# CAN-BUS_FD_HAT_for_Raspberry_Pi.net
KiCad netlist of a schematic drawn in EAGLE
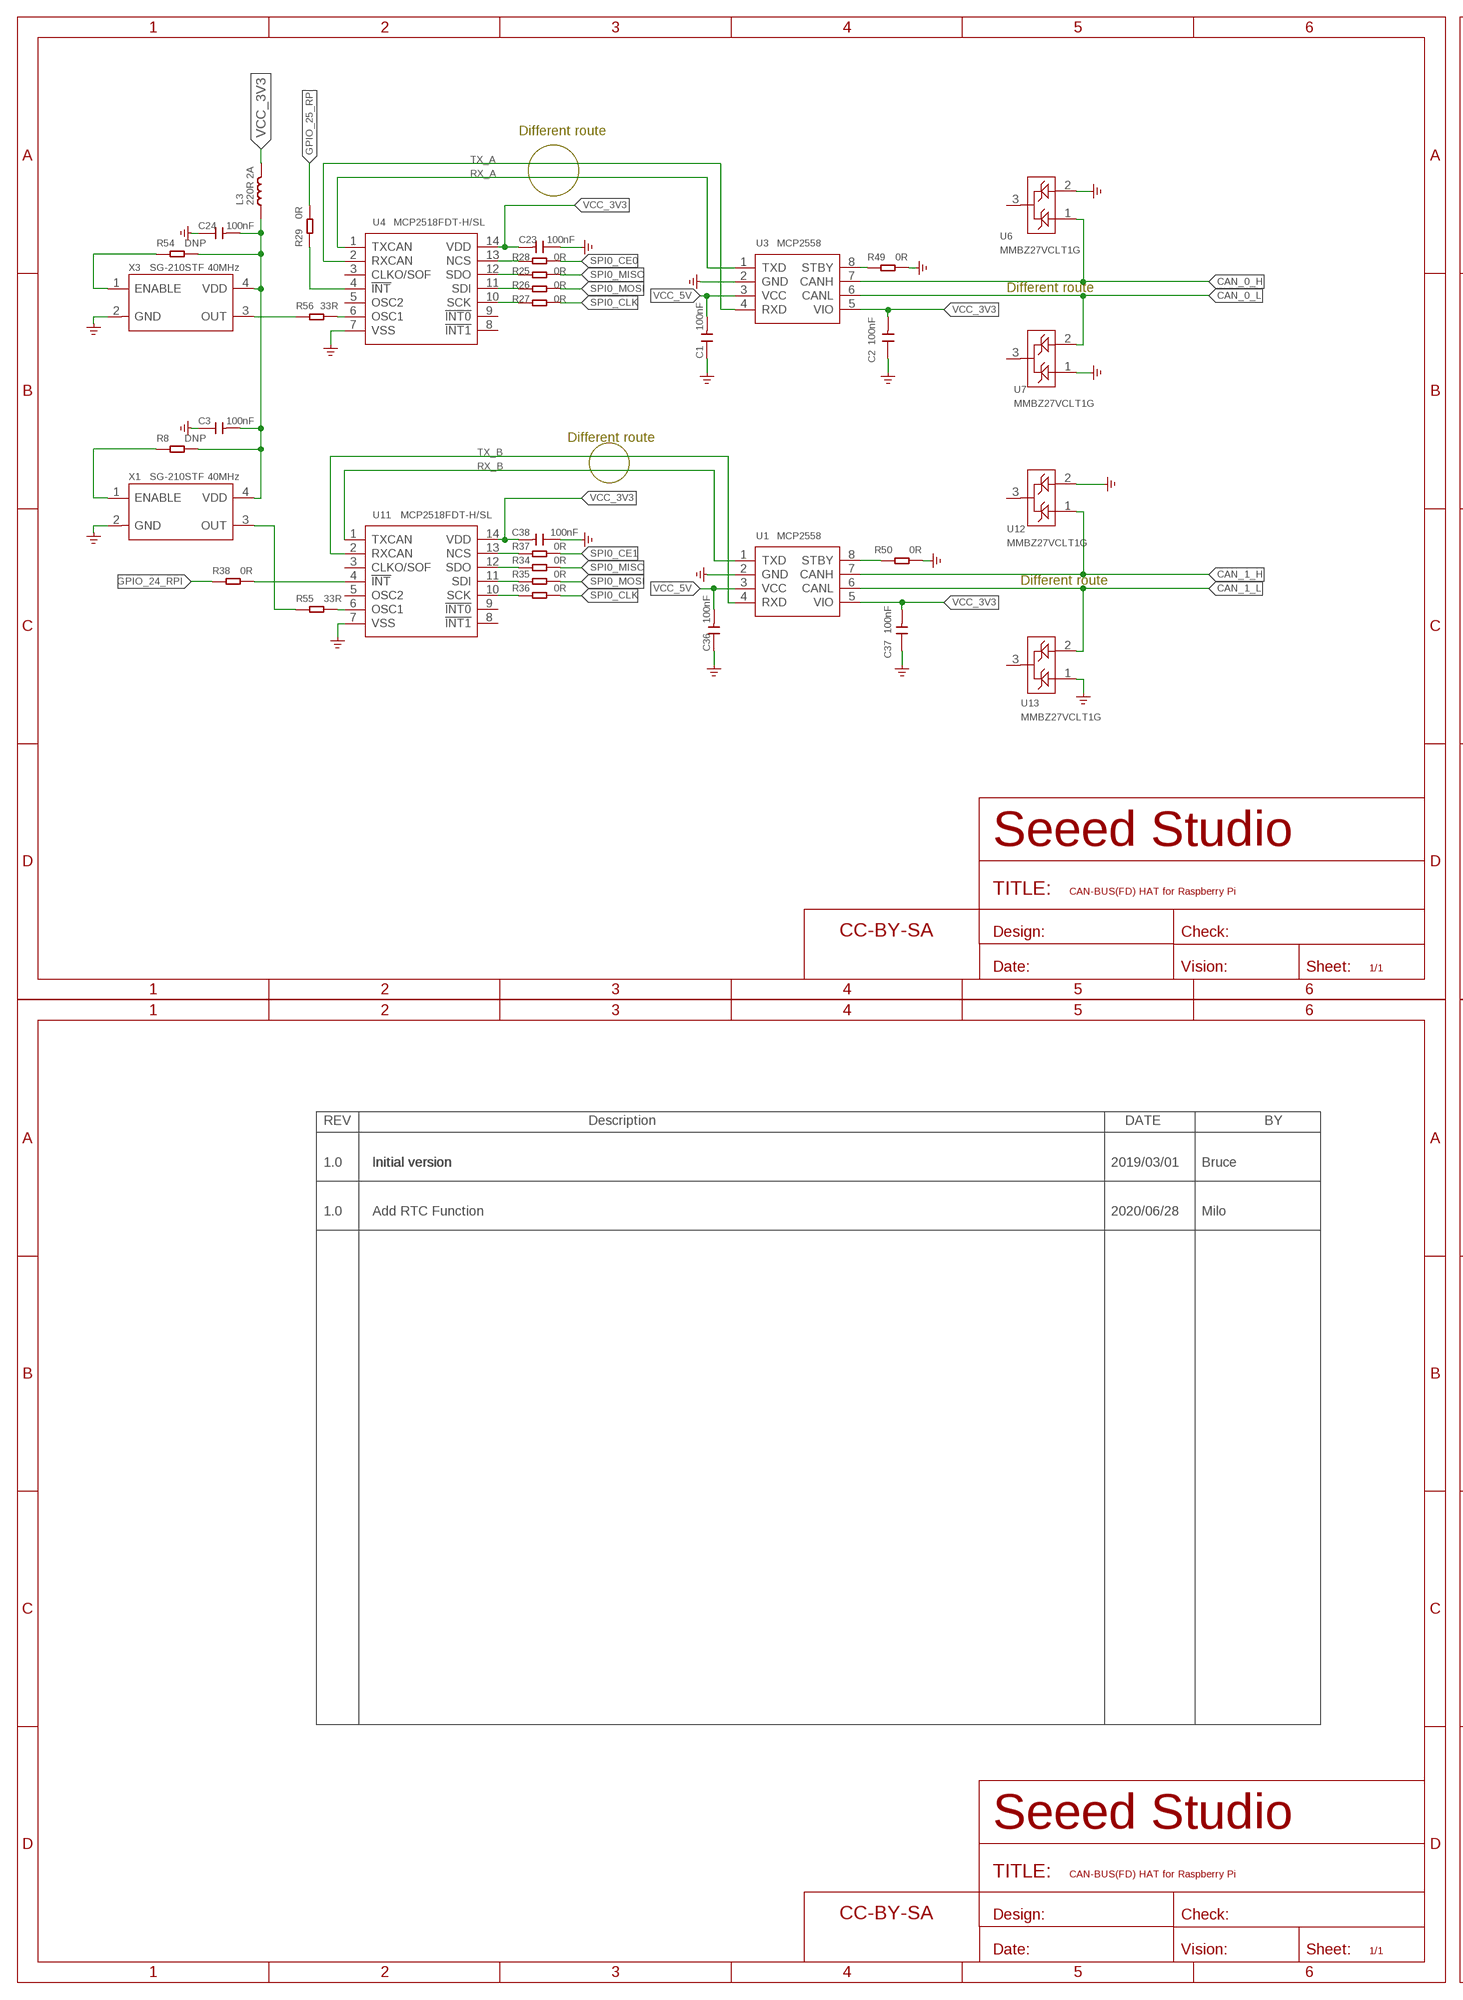
[diagram p0: schematic, sheet 1, part 1 of 2]
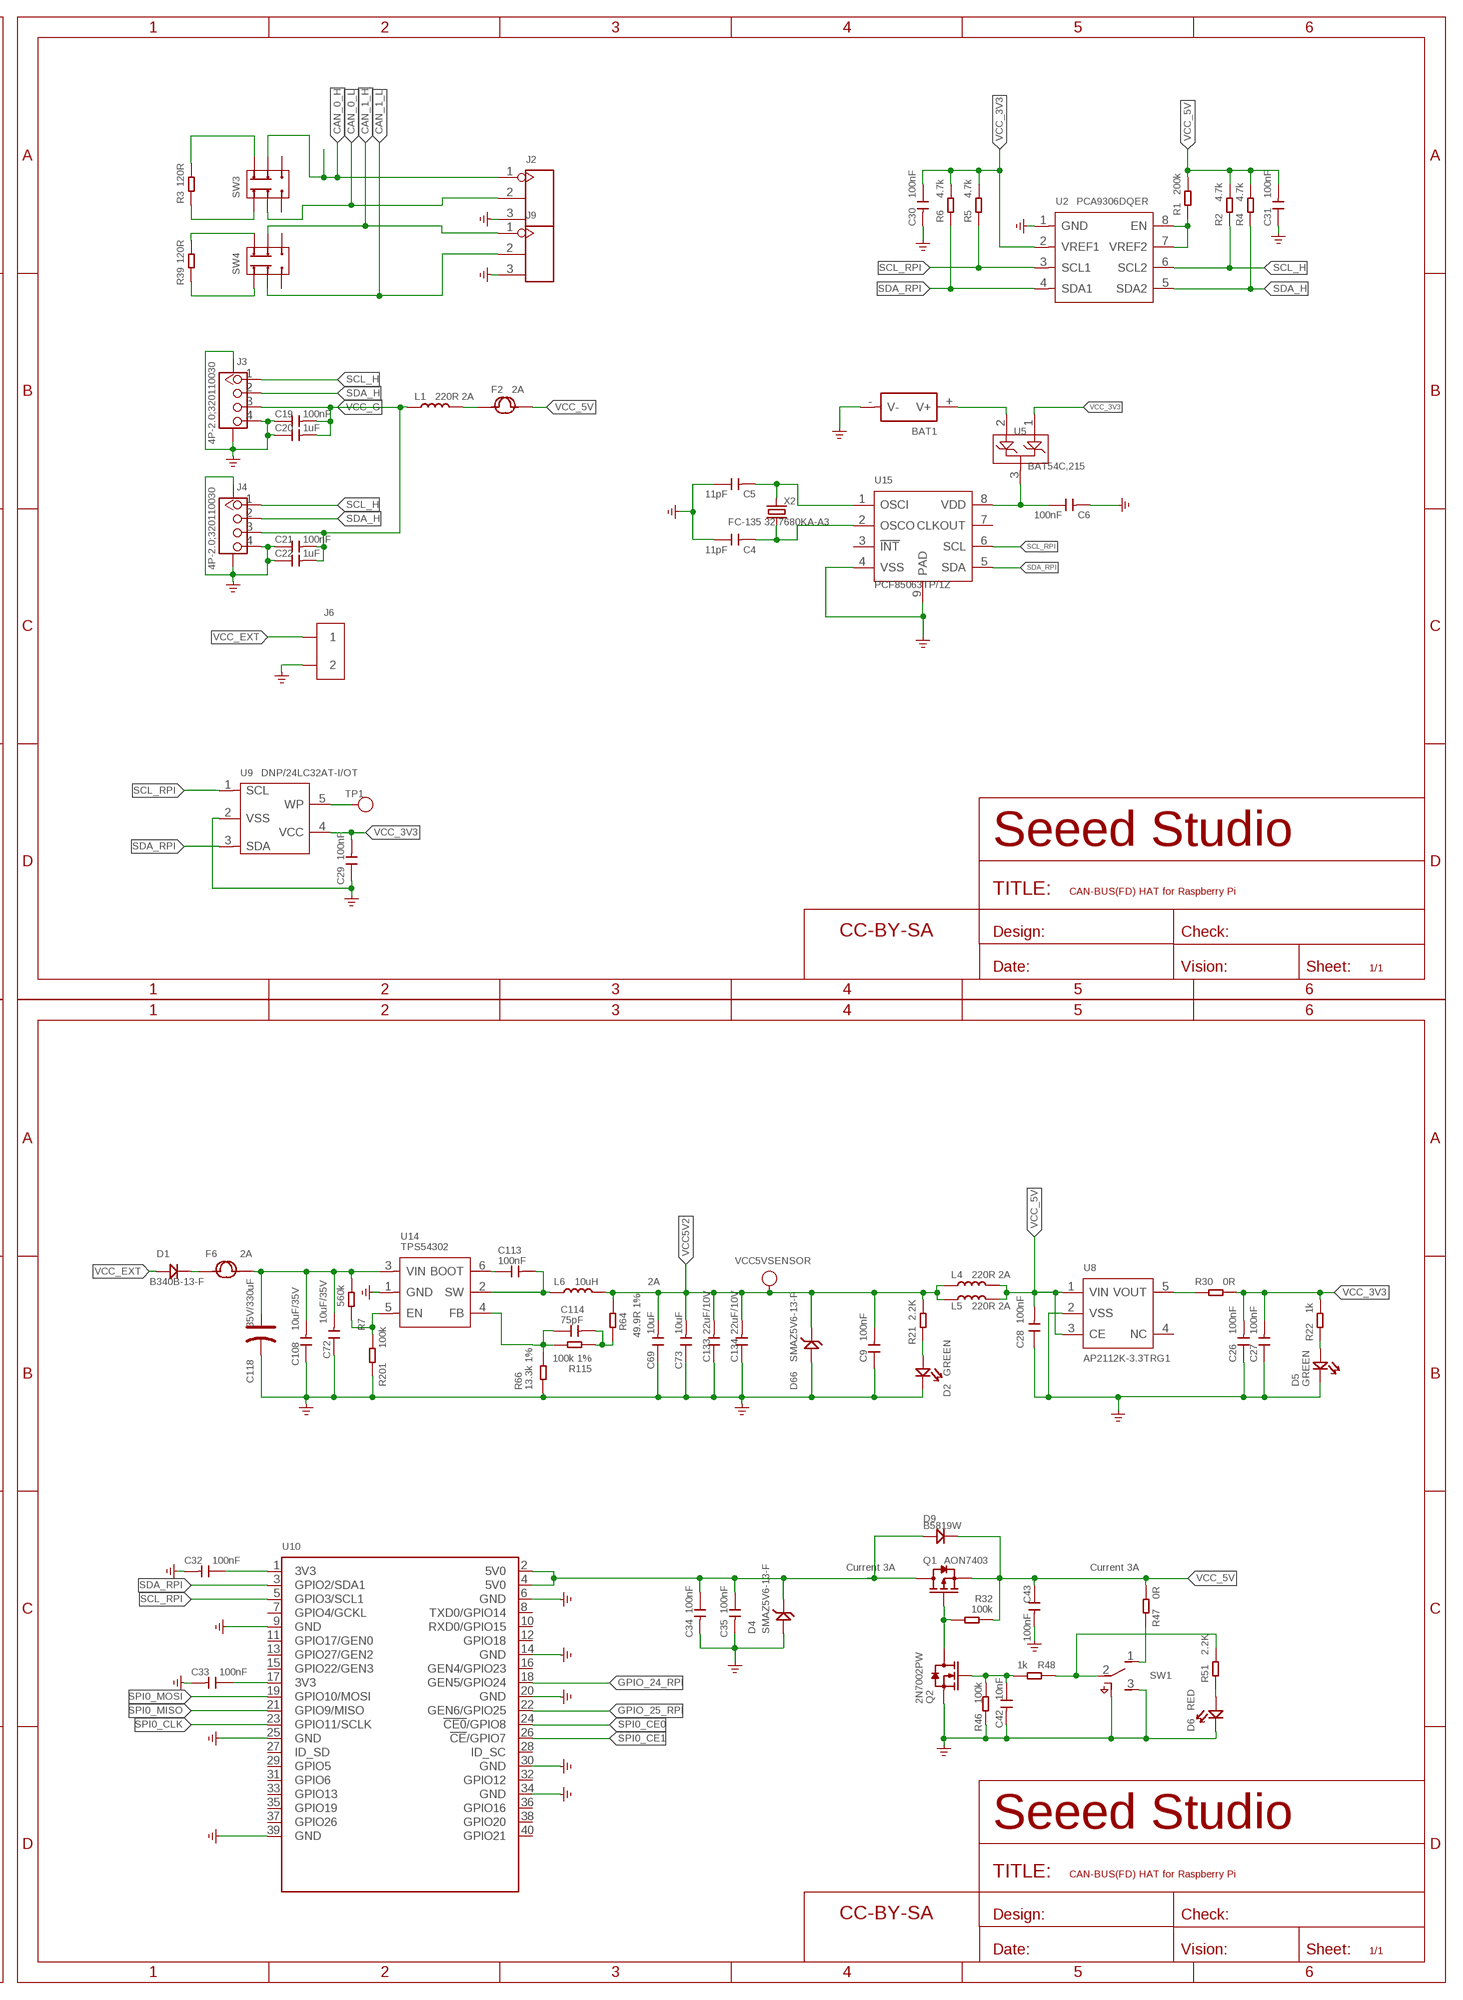
[diagram p1: schematic, sheet 1, part 2 of 2]

(export (version "E")
  (design (tool "Eeschema 10.0.6"))
  (components
    (comp (ref "BAT1")
      (value "BAT-HOLDER'SMD-1220'")
      (footprint "eagle-import:BAT2P-SMD-16.4-CR1220")
      (libsource (lib "eagle-import") (part "BAT-HOLDER'SMD-1220'"))
    )
    (comp (ref "C1")
      (value "100nF")
      (footprint "eagle-import:C0603")
      (libsource (lib "eagle-import") (part "CAP-0603"))
    )
    (comp (ref "C2")
      (value "100nF")
      (footprint "eagle-import:C0603")
      (libsource (lib "eagle-import") (part "CAP-0603"))
    )
    (comp (ref "C3")
      (value "100nF")
      (footprint "eagle-import:C0603")
      (libsource (lib "eagle-import") (part "CAP-0603"))
    )
    (comp (ref "C4")
      (value "11pF")
      (footprint "eagle-import:C0603")
      (libsource (lib "eagle-import") (part "CAP-0603"))
    )
    (comp (ref "C5")
      (value "11pF")
      (footprint "eagle-import:C0603")
      (libsource (lib "eagle-import") (part "CAP-0603"))
    )
    (comp (ref "C6")
      (value "100nF")
      (footprint "eagle-import:C0603")
      (libsource (lib "eagle-import") (part "CAP-0603"))
    )
    (comp (ref "C9")
      (value "100nF")
      (footprint "eagle-import:C0603")
      (libsource (lib "eagle-import") (part "CAP-0603"))
    )
    (comp (ref "C19")
      (value "100nF")
      (footprint "eagle-import:C0603")
      (libsource (lib "eagle-import") (part "CAP-0603"))
    )
    (comp (ref "C20")
      (value "1uF")
      (footprint "eagle-import:C0603")
      (libsource (lib "eagle-import") (part "CAP-0603"))
    )
    (comp (ref "C21")
      (value "100nF")
      (footprint "eagle-import:C0603")
      (libsource (lib "eagle-import") (part "CAP-0603"))
    )
    (comp (ref "C22")
      (value "1uF")
      (footprint "eagle-import:C0603")
      (libsource (lib "eagle-import") (part "CAP-0603"))
    )
    (comp (ref "C23")
      (value "100nF")
      (footprint "eagle-import:C0603")
      (libsource (lib "eagle-import") (part "CAP-0603"))
    )
    (comp (ref "C24")
      (value "100nF")
      (footprint "eagle-import:C0603")
      (libsource (lib "eagle-import") (part "CAP-0603"))
    )
    (comp (ref "C26")
      (value "100nF")
      (footprint "eagle-import:C0603")
      (libsource (lib "eagle-import") (part "CAP-0603"))
    )
    (comp (ref "C27")
      (value "100nF")
      (footprint "eagle-import:C0603")
      (libsource (lib "eagle-import") (part "CAP-0603"))
    )
    (comp (ref "C28")
      (value "100nF")
      (footprint "eagle-import:C0603")
      (libsource (lib "eagle-import") (part "CAP-0603"))
    )
    (comp (ref "C29")
      (value "100nF")
      (footprint "eagle-import:C0603")
      (libsource (lib "eagle-import") (part "CAP-0603"))
    )
    (comp (ref "C30")
      (value "100nF")
      (footprint "eagle-import:C0603")
      (libsource (lib "eagle-import") (part "CAP-0603"))
    )
    (comp (ref "C31")
      (value "100nF")
      (footprint "eagle-import:C0603")
      (libsource (lib "eagle-import") (part "CAP-0603"))
    )
    (comp (ref "C32")
      (value "100nF")
      (footprint "eagle-import:C0603")
      (libsource (lib "eagle-import") (part "CAP-0603"))
    )
    (comp (ref "C33")
      (value "100nF")
      (footprint "eagle-import:C0603")
      (libsource (lib "eagle-import") (part "CAP-0603"))
    )
    (comp (ref "C34")
      (value "100nF")
      (footprint "eagle-import:C0603")
      (libsource (lib "eagle-import") (part "CAP-0603"))
    )
    (comp (ref "C35")
      (value "100nF")
      (footprint "eagle-import:C0603")
      (libsource (lib "eagle-import") (part "CAP-0603"))
    )
    (comp (ref "C36")
      (value "100nF")
      (footprint "eagle-import:C0603")
      (libsource (lib "eagle-import") (part "CAP-0603"))
    )
    (comp (ref "C37")
      (value "100nF")
      (footprint "eagle-import:C0603")
      (libsource (lib "eagle-import") (part "CAP-0603"))
    )
    (comp (ref "C38")
      (value "100nF")
      (footprint "eagle-import:C0603")
      (libsource (lib "eagle-import") (part "CAP-0603"))
    )
    (comp (ref "C42")
      (value "10nF")
      (footprint "eagle-import:C0603")
      (libsource (lib "eagle-import") (part "CAP-0603"))
    )
    (comp (ref "C43")
      (value "100nF")
      (footprint "eagle-import:C0603")
      (libsource (lib "eagle-import") (part "CAP-0603"))
    )
    (comp (ref "C69")
      (value "10uF")
      (footprint "eagle-import:C0805")
      (libsource (lib "eagle-import") (part "CAP-0805"))
    )
    (comp (ref "C72")
      (value "10uF/35V")
      (footprint "eagle-import:C0805")
      (libsource (lib "eagle-import") (part "CAP-0805"))
    )
    (comp (ref "C73")
      (value "10uF")
      (footprint "eagle-import:C0805")
      (libsource (lib "eagle-import") (part "CAP-0805"))
    )
    (comp (ref "C108")
      (value "10uF/35V")
      (footprint "eagle-import:C0805")
      (libsource (lib "eagle-import") (part "CAP-0805"))
    )
    (comp (ref "C113")
      (value "100nF")
      (footprint "eagle-import:C0603")
      (libsource (lib "eagle-import") (part "CAP-0603"))
    )
    (comp (ref "C114")
      (value "75pF")
      (footprint "eagle-import:C0603")
      (libsource (lib "eagle-import") (part "CAP-0603"))
    )
    (comp (ref "C118")
      (value "35V/330uF")
      (footprint "eagle-import:ELECTRO-SMD-E-7.8MM")
      (libsource (lib "eagle-import") (part "CAP-POLAR-ELECTRO-E"))
    )
    (comp (ref "C133")
      (value "22uF/10V")
      (footprint "eagle-import:C1206")
      (libsource (lib "eagle-import") (part "CAP-1206"))
    )
    (comp (ref "C134")
      (value "22uF/10V")
      (footprint "eagle-import:C1206")
      (libsource (lib "eagle-import") (part "CAP-1206"))
    )
    (comp (ref "D1")
      (value "B340B-13-F")
      (footprint "eagle-import:DO-214AA")
      (libsource (lib "eagle-import") (part "Discrete-new_DIODE'SMB'"))
    )
    (comp (ref "D2")
      (value "GREEN")
      (footprint "eagle-import:LED-0603")
      (libsource (lib "eagle-import") (part "LED'0603'"))
    )
    (comp (ref "D4")
      (value "SMAZ5V6-13-F")
      (footprint "eagle-import:DO-214AC")
      (libsource (lib "eagle-import") (part "D-ZENER-2P-SMA"))
    )
    (comp (ref "D5")
      (value "GREEN")
      (footprint "eagle-import:LED-0603")
      (libsource (lib "eagle-import") (part "LED'0603'"))
    )
    (comp (ref "D6")
      (value "RED")
      (footprint "eagle-import:LED-0603")
      (libsource (lib "eagle-import") (part "LED'0603'"))
    )
    (comp (ref "D9")
      (value "B5819W")
      (footprint "eagle-import:SOD-123")
      (libsource (lib "eagle-import") (part "Discrete-new_DIODE'1206'"))
    )
    (comp (ref "D66")
      (value "SMAZ5V6-13-F")
      (footprint "eagle-import:DO-214AC")
      (libsource (lib "eagle-import") (part "D-ZENER-2P-SMA"))
    )
    (comp (ref "F2")
      (value "2A")
      (footprint "eagle-import:FS1210")
      (libsource (lib "eagle-import") (part "FUSE+'1210'"))
    )
    (comp (ref "F6")
      (value "2A")
      (footprint "eagle-import:F1812")
      (libsource (lib "eagle-import") (part "FUSE'1812'"))
    )
    (comp (ref "FR1")
      (value "SEEEDSTUDIO-OPEN-SCH-FRAME")
      (footprint "eagle-import:SEEEDSTUDIO-PCB-FRAME")
      (libsource (lib "eagle-import") (part "SEEEDSTUDIO-OPEN-SCH-FRAME"))
    )
    (comp (ref "FR2")
      (value "SEEEDSTUDIO-OPEN-SCH-FRAME")
      (footprint "eagle-import:SEEEDSTUDIO-PCB-FRAME")
      (libsource (lib "eagle-import") (part "SEEEDSTUDIO-OPEN-SCH-FRAME"))
    )
    (comp (ref "FR3")
      (value "SEEEDSTUDIO-OPEN-SCH-FRAME")
      (footprint "eagle-import:SEEEDSTUDIO-PCB-FRAME")
      (libsource (lib "eagle-import") (part "SEEEDSTUDIO-OPEN-SCH-FRAME"))
    )
    (comp (ref "FR5")
      (value "SEEEDSTUDIO-OPEN-SCH-FRAME")
      (footprint "eagle-import:SEEEDSTUDIO-PCB-FRAME")
      (libsource (lib "eagle-import") (part "SEEEDSTUDIO-OPEN-SCH-FRAME"))
    )
    (comp (ref "J2")
      (value "SCREW-TERMINAL-3P'3.5'")
      (footprint "eagle-import:H3-3.5-11.5X7.0MM")
      (libsource (lib "eagle-import") (part "SCREW-TERMINAL-3P'3.5'"))
    )
    (comp (ref "J3")
      (value "4P-2.0;320110030")
      (footprint "eagle-import:HW4-SMD-2.0")
      (libsource (lib "eagle-import") (part "GROVE-CONNECTOR-SMD'DD'"))
    )
    (comp (ref "J4")
      (value "4P-2.0;320110030")
      (footprint "eagle-import:HW4-SMD-2.0")
      (libsource (lib "eagle-import") (part "GROVE-CONNECTOR-SMD'DD'"))
    )
    (comp (ref "J6")
      (value "SCREW-TERMINAL-2P'3.5'")
      (footprint "eagle-import:H2-3.5-7.0X7.0MM")
      (libsource (lib "eagle-import") (part "SCREW-TERMINAL-2P'3.5'"))
    )
    (comp (ref "J9")
      (value "SCREW-TERMINAL-3P'3.5'")
      (footprint "eagle-import:H3-3.5-11.5X7.0MM")
      (libsource (lib "eagle-import") (part "SCREW-TERMINAL-3P'3.5'"))
    )
    (comp (ref "L1")
      (value "220R 2A")
      (footprint "eagle-import:L0805")
      (libsource (lib "eagle-import") (part "INDUCTOR/FERRITE-BEAD'0805'"))
    )
    (comp (ref "L3")
      (value "220R 2A")
      (footprint "eagle-import:L0805")
      (libsource (lib "eagle-import") (part "INDUCTOR/FERRITE-BEAD'0805'"))
    )
    (comp (ref "L4")
      (value "220R 2A")
      (footprint "eagle-import:L0805")
      (libsource (lib "eagle-import") (part "INDUCTOR/FERRITE-BEAD'0805'"))
    )
    (comp (ref "L5")
      (value "220R 2A")
      (footprint "eagle-import:L0805")
      (libsource (lib "eagle-import") (part "INDUCTOR/FERRITE-BEAD'0805'"))
    )
    (comp (ref "L6")
      (value "10uH")
      (footprint "eagle-import:L8040")
      (libsource (lib "eagle-import") (part "INDUCTOR-8040"))
    )
    (comp (ref "Q1")
      (value "AON7403")
      (footprint "eagle-import:DFN8P-0.65-3X3X0.8MM")
      (libsource (lib "eagle-import") (part "MOSFET-P-AON7403"))
    )
    (comp (ref "Q2")
      (value "2N7002PW")
      (footprint "eagle-import:SOT-23")
      (libsource (lib "eagle-import") (part "MOSFET-N'SOT23'"))
    )
    (comp (ref "R1")
      (value "200k")
      (footprint "eagle-import:R0603")
      (libsource (lib "eagle-import") (part "RES-0603"))
    )
    (comp (ref "R2")
      (value "4.7k")
      (footprint "eagle-import:R0603")
      (libsource (lib "eagle-import") (part "RES-0603"))
    )
    (comp (ref "R3")
      (value "120R")
      (footprint "eagle-import:R1206")
      (libsource (lib "eagle-import") (part "RES-1206"))
    )
    (comp (ref "R4")
      (value "4.7k")
      (footprint "eagle-import:R0603")
      (libsource (lib "eagle-import") (part "RES-0603"))
    )
    (comp (ref "R5")
      (value "4.7k")
      (footprint "eagle-import:R0603")
      (libsource (lib "eagle-import") (part "RES-0603"))
    )
    (comp (ref "R6")
      (value "4.7k")
      (footprint "eagle-import:R0603")
      (libsource (lib "eagle-import") (part "RES-0603"))
    )
    (comp (ref "R7")
      (value "560k")
      (footprint "eagle-import:R0603")
      (libsource (lib "eagle-import") (part "RES-0603"))
    )
    (comp (ref "R8")
      (value "DNP")
      (footprint "eagle-import:0603")
      (libsource (lib "eagle-import") (part "R-0603"))
    )
    (comp (ref "R21")
      (value "2.2K")
      (footprint "eagle-import:0603")
      (libsource (lib "eagle-import") (part "R-0603"))
    )
    (comp (ref "R22")
      (value "1k")
      (footprint "eagle-import:0603")
      (libsource (lib "eagle-import") (part "R-0603"))
    )
    (comp (ref "R25")
      (value "0R")
      (footprint "eagle-import:0603")
      (libsource (lib "eagle-import") (part "R-0603"))
    )
    (comp (ref "R26")
      (value "0R")
      (footprint "eagle-import:0603")
      (libsource (lib "eagle-import") (part "R-0603"))
    )
    (comp (ref "R27")
      (value "0R")
      (footprint "eagle-import:0603")
      (libsource (lib "eagle-import") (part "R-0603"))
    )
    (comp (ref "R28")
      (value "0R")
      (footprint "eagle-import:0603")
      (libsource (lib "eagle-import") (part "R-0603"))
    )
    (comp (ref "R29")
      (value "0R")
      (footprint "eagle-import:0603")
      (libsource (lib "eagle-import") (part "R-0603"))
    )
    (comp (ref "R30")
      (value "0R")
      (footprint "eagle-import:R0603")
      (libsource (lib "eagle-import") (part "RES-0603"))
    )
    (comp (ref "R32")
      (value "100k")
      (footprint "eagle-import:0603")
      (libsource (lib "eagle-import") (part "R-0603"))
    )
    (comp (ref "R34")
      (value "0R")
      (footprint "eagle-import:0603")
      (libsource (lib "eagle-import") (part "R-0603"))
    )
    (comp (ref "R35")
      (value "0R")
      (footprint "eagle-import:0603")
      (libsource (lib "eagle-import") (part "R-0603"))
    )
    (comp (ref "R36")
      (value "0R")
      (footprint "eagle-import:0603")
      (libsource (lib "eagle-import") (part "R-0603"))
    )
    (comp (ref "R37")
      (value "0R")
      (footprint "eagle-import:0603")
      (libsource (lib "eagle-import") (part "R-0603"))
    )
    (comp (ref "R38")
      (value "0R")
      (footprint "eagle-import:0603")
      (libsource (lib "eagle-import") (part "R-0603"))
    )
    (comp (ref "R39")
      (value "120R")
      (footprint "eagle-import:R1206")
      (libsource (lib "eagle-import") (part "RES-1206"))
    )
    (comp (ref "R46")
      (value "100k")
      (footprint "eagle-import:0603")
      (libsource (lib "eagle-import") (part "R-0603"))
    )
    (comp (ref "R47")
      (value "0R")
      (footprint "eagle-import:0603")
      (libsource (lib "eagle-import") (part "R-0603"))
    )
    (comp (ref "R48")
      (value "1k")
      (footprint "eagle-import:0603")
      (libsource (lib "eagle-import") (part "R-0603"))
    )
    (comp (ref "R49")
      (value "0R")
      (footprint "eagle-import:0603")
      (libsource (lib "eagle-import") (part "R-0603"))
    )
    (comp (ref "R50")
      (value "0R")
      (footprint "eagle-import:0603")
      (libsource (lib "eagle-import") (part "R-0603"))
    )
    (comp (ref "R51")
      (value "2.2K")
      (footprint "eagle-import:0603")
      (libsource (lib "eagle-import") (part "R-0603"))
    )
    (comp (ref "R54")
      (value "DNP")
      (footprint "eagle-import:0603")
      (libsource (lib "eagle-import") (part "R-0603"))
    )
    (comp (ref "R55")
      (value "33R")
      (footprint "eagle-import:0603")
      (libsource (lib "eagle-import") (part "R-0603"))
    )
    (comp (ref "R56")
      (value "33R")
      (footprint "eagle-import:0603")
      (libsource (lib "eagle-import") (part "R-0603"))
    )
    (comp (ref "R64")
      (value "49.9R 1%")
      (footprint "eagle-import:R0603")
      (libsource (lib "eagle-import") (part "RES-0603"))
    )
    (comp (ref "R66")
      (value "13.3k 1%")
      (footprint "eagle-import:R0603")
      (libsource (lib "eagle-import") (part "RES-0603"))
    )
    (comp (ref "R115")
      (value "100k 1%")
      (footprint "eagle-import:R0603")
      (libsource (lib "eagle-import") (part "RES-0603"))
    )
    (comp (ref "R201")
      (value "100k")
      (footprint "eagle-import:R0603")
      (libsource (lib "eagle-import") (part "RES-0603"))
    )
    (comp (ref "SW1")
      (value "SWITCH-3+4P-311030001")
      (footprint "eagle-import:SW7-SMD-L6.7X2.7X3.2MM")
      (libsource (lib "eagle-import") (part "SWITCH-3+4P-311030001"))
    )
    (comp (ref "SW3")
      (value "SWITCH-2CH-6P-311010004")
      (footprint "eagle-import:SW6-2.54-9.0X3.5X3.2+2.0MM")
      (libsource (lib "eagle-import") (part "SWITCH-2CH-6P-311010004"))
    )
    (comp (ref "SW4")
      (value "SWITCH-2CH-6P-311010004")
      (footprint "eagle-import:SW6-2.54-9.0X3.5X3.2+2.0MM")
      (libsource (lib "eagle-import") (part "SWITCH-2CH-6P-311010004"))
    )
    (comp (ref "TP1")
      (value "DNP")
      (footprint "eagle-import:TP-D45MIL")
      (libsource (lib "eagle-import") (part "TEST-POINT'4545'"))
    )
    (comp (ref "U1")
      (value "MCP2558")
      (footprint "eagle-import:SOIC8-1.27-5X4MM")
      (libsource (lib "eagle-import") (part "TRANSCEIVER-ATA6561'GAQW'"))
    )
    (comp (ref "U2")
      (value "PCA9306DQER")
      (footprint "eagle-import:X2SON8-0.35-1.4X1X0.37MM")
      (libsource (lib "eagle-import") (part "TRANSLATOR-PCA9306DQER"))
    )
    (comp (ref "U3")
      (value "MCP2558")
      (footprint "eagle-import:SOIC8-1.27-5X4MM")
      (libsource (lib "eagle-import") (part "TRANSCEIVER-ATA6561'GAQW'"))
    )
    (comp (ref "U4")
      (value "MCP2518FDT-H/SL")
      (footprint "eagle-import:SOIC14-1.27-8.65X3.9MM")
      (libsource (lib "eagle-import") (part "INTERFACE-MCP2517FD'H/SL'"))
    )
    (comp (ref "U5")
      (value "BAT54C,215")
      (footprint "eagle-import:SOT-23")
      (libsource (lib "eagle-import") (part "DIODE-BAT54C"))
    )
    (comp (ref "U6")
      (value "MMBZ27VCLT1G")
      (footprint "eagle-import:SOT-23")
      (libsource (lib "eagle-import") (part "DIODE-BAT54C"))
    )
    (comp (ref "U7")
      (value "MMBZ27VCLT1G")
      (footprint "eagle-import:SOT-23")
      (libsource (lib "eagle-import") (part "DIODE-BAT54C"))
    )
    (comp (ref "U8")
      (value "AP2112K-3.3TRG1")
      (footprint "eagle-import:SOT-25")
      (libsource (lib "eagle-import") (part "PMIC-XC6220-SOT-25"))
    )
    (comp (ref "U9")
      (value "DNP/24LC32AT-I/OT")
      (footprint "eagle-import:SOT-23-5")
      (libsource (lib "eagle-import") (part "MEMORY-24LC32A'310090051'"))
    )
    (comp (ref "U10")
      (value "RPI-ZERO-SMD/NP")
      (footprint "eagle-import:H2X20-SMD_NP-2.54")
      (libsource (lib "eagle-import") (part "RPI-ZERO-SMD/NP"))
    )
    (comp (ref "U11")
      (value "MCP2518FDT-H/SL")
      (footprint "eagle-import:SOIC14-1.27-8.65X3.9MM")
      (libsource (lib "eagle-import") (part "INTERFACE-MCP2517FD'H/SL'"))
    )
    (comp (ref "U12")
      (value "MMBZ27VCLT1G")
      (footprint "eagle-import:SOT-23")
      (libsource (lib "eagle-import") (part "DIODE-BAT54C"))
    )
    (comp (ref "U13")
      (value "MMBZ27VCLT1G")
      (footprint "eagle-import:SOT-23")
      (libsource (lib "eagle-import") (part "DIODE-BAT54C"))
    )
    (comp (ref "U14")
      (value "TPS54302")
      (footprint "eagle-import:SOT-23-6")
      (libsource (lib "eagle-import") (part "PMIC-TPS54302"))
    )
    (comp (ref "U15")
      (value "PCF85063TP/1Z")
      (footprint "eagle-import:HWSON8-0.5-2X3X0.75MM")
      (libsource (lib "eagle-import") (part "RTC-PCF85063TP"))
    )
    (comp (ref "VCC5VSENSOR")
      (value "DNP")
      (footprint "eagle-import:TP-D45MIL")
      (libsource (lib "eagle-import") (part "TEST-POINT'4545'"))
    )
    (comp (ref "X1")
      (value "SG-210STF 40MHz")
      (footprint "eagle-import:X4-SMD-2.5X2.0X1.0MM")
      (libsource (lib "eagle-import") (part "CRYSTAL-OSCILLATOR-2520"))
    )
    (comp (ref "X2")
      (value "FC-135 32.7680KA-A3")
      (footprint "eagle-import:X2-SMD-3.2X1.5X0.55MM")
      (libsource (lib "eagle-import") (part "CRYSTAL-2P-3215"))
    )
    (comp (ref "X3")
      (value "SG-210STF 40MHz")
      (footprint "eagle-import:X4-SMD-2.5X2.0X1.0MM")
      (libsource (lib "eagle-import") (part "CRYSTAL-OSCILLATOR-2520"))
    )
  )
  (nets
    (net (code "1") (name "/RX_A") (class "Default")
      (node (ref "U3") (pin "1") (pinfunction "TXD_1") (pintype "bidirectional"))
      (node (ref "U4") (pin "1") (pinfunction "TXCAN_1") (pintype "bidirectional"))
    )
    (net (code "2") (name "/RX_B") (class "Default")
      (node (ref "U1") (pin "1") (pinfunction "TXD_1") (pintype "bidirectional"))
      (node (ref "U11") (pin "1") (pinfunction "TXCAN_1") (pintype "bidirectional"))
    )
    (net (code "3") (name "/TX_A") (class "Default")
      (node (ref "U3") (pin "4") (pinfunction "RXD_4") (pintype "bidirectional"))
      (node (ref "U4") (pin "2") (pinfunction "RXCAN_2") (pintype "bidirectional"))
    )
    (net (code "4") (name "/TX_B") (class "Default")
      (node (ref "U1") (pin "4") (pinfunction "RXD_4") (pintype "bidirectional"))
      (node (ref "U11") (pin "2") (pinfunction "RXCAN_2") (pintype "bidirectional"))
    )
    (net (code "5") (name "CAN_0_H") (class "Default")
      (node (ref "J2") (pin "1") (pinfunction "P$1_1") (pintype "bidirectional"))
      (node (ref "SW3") (pin "COM2") (pinfunction "COM2_COM2") (pintype "bidirectional"))
      (node (ref "U3") (pin "7") (pinfunction "CANH_7") (pintype "bidirectional"))
      (node (ref "U6") (pin "1") (pinfunction "P$1_1") (pintype "bidirectional"))
    )
    (net (code "6") (name "CAN_0_L") (class "Default")
      (node (ref "J2") (pin "2") (pinfunction "P$2_2") (pintype "bidirectional"))
      (node (ref "SW3") (pin "COM1") (pinfunction "COM1_COM1") (pintype "bidirectional"))
      (node (ref "U3") (pin "6") (pinfunction "CANL_6") (pintype "bidirectional"))
      (node (ref "U7") (pin "2") (pinfunction "P$2_2") (pintype "bidirectional"))
    )
    (net (code "7") (name "CAN_1_H") (class "Default")
      (node (ref "J9") (pin "1") (pinfunction "P$1_1") (pintype "bidirectional"))
      (node (ref "SW4") (pin "COM2") (pinfunction "COM2_COM2") (pintype "bidirectional"))
      (node (ref "U1") (pin "7") (pinfunction "CANH_7") (pintype "bidirectional"))
      (node (ref "U12") (pin "1") (pinfunction "P$1_1") (pintype "bidirectional"))
    )
    (net (code "8") (name "CAN_1_L") (class "Default")
      (node (ref "J9") (pin "2") (pinfunction "P$2_2") (pintype "bidirectional"))
      (node (ref "SW4") (pin "COM1") (pinfunction "COM1_COM1") (pintype "bidirectional"))
      (node (ref "U1") (pin "6") (pinfunction "CANL_6") (pintype "bidirectional"))
      (node (ref "U13") (pin "2") (pinfunction "P$2_2") (pintype "bidirectional"))
    )
    (net (code "9") (name "GND_POWER") (class "Default")
      (node (ref "BAT1") (pin "-") (pinfunction "V-_-") (pintype "bidirectional"))
      (node (ref "C1") (pin "1") (pinfunction "1_1") (pintype "passive"))
      (node (ref "C108") (pin "1") (pinfunction "1_1") (pintype "passive"))
      (node (ref "C118") (pin "-") (pinfunction "-_-") (pintype "passive"))
      (node (ref "C133") (pin "1") (pinfunction "1_1") (pintype "passive"))
      (node (ref "C134") (pin "1") (pinfunction "1_1") (pintype "passive"))
      (node (ref "C19") (pin "1") (pinfunction "1_1") (pintype "passive"))
      (node (ref "C2") (pin "1") (pinfunction "1_1") (pintype "passive"))
      (node (ref "C20") (pin "1") (pinfunction "1_1") (pintype "passive"))
      (node (ref "C21") (pin "1") (pinfunction "1_1") (pintype "passive"))
      (node (ref "C22") (pin "1") (pinfunction "1_1") (pintype "passive"))
      (node (ref "C23") (pin "1") (pinfunction "1_1") (pintype "passive"))
      (node (ref "C24") (pin "1") (pinfunction "1_1") (pintype "passive"))
      (node (ref "C26") (pin "1") (pinfunction "1_1") (pintype "passive"))
      (node (ref "C27") (pin "1") (pinfunction "1_1") (pintype "passive"))
      (node (ref "C28") (pin "1") (pinfunction "1_1") (pintype "passive"))
      (node (ref "C29") (pin "1") (pinfunction "1_1") (pintype "passive"))
      (node (ref "C3") (pin "1") (pinfunction "1_1") (pintype "passive"))
      (node (ref "C30") (pin "2") (pinfunction "2_2") (pintype "passive"))
      (node (ref "C31") (pin "1") (pinfunction "1_1") (pintype "passive"))
      (node (ref "C32") (pin "2") (pinfunction "2_2") (pintype "passive"))
      (node (ref "C33") (pin "2") (pinfunction "2_2") (pintype "passive"))
      (node (ref "C34") (pin "2") (pinfunction "2_2") (pintype "passive"))
      (node (ref "C35") (pin "2") (pinfunction "2_2") (pintype "passive"))
      (node (ref "C36") (pin "1") (pinfunction "1_1") (pintype "passive"))
      (node (ref "C37") (pin "1") (pinfunction "1_1") (pintype "passive"))
      (node (ref "C38") (pin "1") (pinfunction "1_1") (pintype "passive"))
      (node (ref "C4") (pin "1") (pinfunction "1_1") (pintype "passive"))
      (node (ref "C42") (pin "2") (pinfunction "2_2") (pintype "passive"))
      (node (ref "C43") (pin "2") (pinfunction "2_2") (pintype "passive"))
      (node (ref "C5") (pin "1") (pinfunction "1_1") (pintype "passive"))
      (node (ref "C6") (pin "2") (pinfunction "2_2") (pintype "passive"))
      (node (ref "C69") (pin "1") (pinfunction "1_1") (pintype "passive"))
      (node (ref "C72") (pin "1") (pinfunction "1_1") (pintype "passive"))
      (node (ref "C73") (pin "1") (pinfunction "1_1") (pintype "passive"))
      (node (ref "C9") (pin "1") (pinfunction "1_1") (pintype "passive"))
      (node (ref "D2") (pin "-") (pinfunction "-_-") (pintype "passive"))
      (node (ref "D4") (pin "1") (pinfunction "+_1") (pintype "bidirectional"))
      (node (ref "D5") (pin "-") (pinfunction "-_-") (pintype "passive"))
      (node (ref "D6") (pin "-") (pinfunction "-_-") (pintype "passive"))
      (node (ref "D66") (pin "1") (pinfunction "+_1") (pintype "bidirectional"))
      (node (ref "J2") (pin "3") (pinfunction "P$3_3") (pintype "bidirectional"))
      (node (ref "J3") (pin "4") (pinfunction "4_4") (pintype "bidirectional"))
      (node (ref "J3") (pin "SS1") (pinfunction "SS1_SS1") (pintype "bidirectional"))
      (node (ref "J3") (pin "SS2") (pinfunction "SS2_SS2") (pintype "bidirectional"))
      (node (ref "J4") (pin "4") (pinfunction "4_4") (pintype "bidirectional"))
      (node (ref "J4") (pin "SS1") (pinfunction "SS1_SS1") (pintype "bidirectional"))
      (node (ref "J4") (pin "SS2") (pinfunction "SS2_SS2") (pintype "bidirectional"))
      (node (ref "J6") (pin "2") (pinfunction "2_2") (pintype "bidirectional"))
      (node (ref "J9") (pin "3") (pinfunction "P$3_3") (pintype "bidirectional"))
      (node (ref "Q2") (pin "2") (pinfunction "S_2") (pintype "passive"))
      (node (ref "R201") (pin "1") (pinfunction "1_1") (pintype "passive"))
      (node (ref "R46") (pin "1") (pinfunction "1_1") (pintype "passive"))
      (node (ref "R49") (pin "2") (pinfunction "2_2") (pintype "passive"))
      (node (ref "R50") (pin "2") (pinfunction "2_2") (pintype "passive"))
      (node (ref "R66") (pin "1") (pinfunction "1_1") (pintype "passive"))
      (node (ref "SW1") (pin "3") (pinfunction "B_3") (pintype "bidirectional"))
      (node (ref "SW1") (pin "SS1") (pinfunction "SS2_SS1") (pintype "bidirectional"))
      (node (ref "SW1") (pin "SS2") (pinfunction "SS2_SS2") (pintype "bidirectional"))
      (node (ref "SW1") (pin "SS3") (pinfunction "SS2_SS3") (pintype "bidirectional"))
      (node (ref "SW1") (pin "SS4") (pinfunction "SS2_SS4") (pintype "bidirectional"))
      (node (ref "U1") (pin "2") (pinfunction "GND_2") (pintype "bidirectional"))
      (node (ref "U10") (pin "14") (pinfunction "GND_14") (pintype "power_in"))
      (node (ref "U10") (pin "20") (pinfunction "GND_20") (pintype "power_in"))
      (node (ref "U10") (pin "25") (pinfunction "GND_25") (pintype "power_in"))
      (node (ref "U10") (pin "30") (pinfunction "GND_30") (pintype "power_in"))
      (node (ref "U10") (pin "34") (pinfunction "GND_34") (pintype "power_in"))
      (node (ref "U10") (pin "39") (pinfunction "GND_39") (pintype "power_in"))
      (node (ref "U10") (pin "6") (pinfunction "GND_6") (pintype "power_in"))
      (node (ref "U10") (pin "9") (pinfunction "GND_9") (pintype "power_in"))
      (node (ref "U11") (pin "7") (pinfunction "VSS_7") (pintype "bidirectional"))
      (node (ref "U12") (pin "2") (pinfunction "P$2_2") (pintype "bidirectional"))
      (node (ref "U13") (pin "1") (pinfunction "P$1_1") (pintype "bidirectional"))
      (node (ref "U14") (pin "1") (pinfunction "GND_1") (pintype "bidirectional"))
      (node (ref "U15") (pin "4") (pinfunction "VSS_4") (pintype "bidirectional"))
      (node (ref "U15") (pin "9") (pinfunction "PAD_9") (pintype "bidirectional"))
      (node (ref "U2") (pin "1") (pinfunction "GND_1") (pintype "bidirectional"))
      (node (ref "U3") (pin "2") (pinfunction "GND_2") (pintype "bidirectional"))
      (node (ref "U4") (pin "7") (pinfunction "VSS_7") (pintype "bidirectional"))
      (node (ref "U6") (pin "2") (pinfunction "P$2_2") (pintype "bidirectional"))
      (node (ref "U7") (pin "1") (pinfunction "P$1_1") (pintype "bidirectional"))
      (node (ref "U8") (pin "2") (pinfunction "VSS_2") (pintype "bidirectional"))
      (node (ref "U9") (pin "2") (pinfunction "VSS_2") (pintype "bidirectional"))
      (node (ref "X1") (pin "2") (pinfunction "GND_2") (pintype "bidirectional"))
      (node (ref "X3") (pin "2") (pinfunction "GND_2") (pintype "bidirectional"))
    )
    (net (code "10") (name "GPIO_24_RPI") (class "Default")
      (node (ref "R38") (pin "2") (pinfunction "2_2") (pintype "passive"))
      (node (ref "U10") (pin "18") (pinfunction "GEN5/GPIO24_18") (pintype "bidirectional"))
    )
    (net (code "11") (name "GPIO_25_RPI") (class "Default")
      (node (ref "R29") (pin "2") (pinfunction "2_2") (pintype "passive"))
      (node (ref "U10") (pin "22") (pinfunction "GEN6/GPIO25_22") (pintype "bidirectional"))
    )
    (net (code "12") (name "Net-(BAT1-V+)") (class "Default")
      (node (ref "BAT1") (pin "+") (pinfunction "V+_+") (pintype "bidirectional"))
      (node (ref "U5") (pin "2") (pinfunction "P$2_2") (pintype "bidirectional"))
    )
    (net (code "13") (name "Net-(C32-Pad1)") (class "Default")
      (node (ref "C32") (pin "1") (pinfunction "1_1") (pintype "passive"))
      (node (ref "U10") (pin "1") (pinfunction "3V3_1") (pintype "power_in"))
    )
    (net (code "14") (name "Net-(C33-Pad1)") (class "Default")
      (node (ref "C33") (pin "1") (pinfunction "1_1") (pintype "passive"))
      (node (ref "U10") (pin "17") (pinfunction "3V3_17") (pintype "power_in"))
    )
    (net (code "15") (name "Net-(C114-Pad2)") (class "Default")
      (node (ref "C114") (pin "2") (pinfunction "2_2") (pintype "passive"))
      (node (ref "R115") (pin "1") (pinfunction "1_1") (pintype "passive"))
      (node (ref "R64") (pin "1") (pinfunction "1_1") (pintype "passive"))
    )
    (net (code "16") (name "Net-(D1--)") (class "Default")
      (node (ref "D1") (pin "2") (pinfunction "-_2") (pintype "passive"))
      (node (ref "F6") (pin "1") (pinfunction "1_1") (pintype "bidirectional"))
    )
    (net (code "17") (name "Net-(D2-Pad+)") (class "Default")
      (node (ref "D2") (pin "+") (pinfunction "+_+") (pintype "passive"))
      (node (ref "R21") (pin "1") (pinfunction "1_1") (pintype "passive"))
    )
    (net (code "18") (name "Net-(D4--)") (class "Default")
      (node (ref "C34") (pin "1") (pinfunction "1_1") (pintype "passive"))
      (node (ref "C35") (pin "1") (pinfunction "1_1") (pintype "passive"))
      (node (ref "D4") (pin "2") (pinfunction "-_2") (pintype "bidirectional"))
      (node (ref "D9") (pin "+") (pinfunction "+_+") (pintype "passive"))
      (node (ref "Q1") (pin "5") (pinfunction "D_5") (pintype "passive"))
      (node (ref "Q1") (pin "6") (pinfunction "D_6") (pintype "passive"))
      (node (ref "Q1") (pin "7") (pinfunction "D_7") (pintype "passive"))
      (node (ref "Q1") (pin "8") (pinfunction "D_8") (pintype "passive"))
      (node (ref "U10") (pin "2") (pinfunction "5V0_2") (pintype "power_in"))
      (node (ref "U10") (pin "4") (pinfunction "5V0_4") (pintype "power_in"))
    )
    (net (code "19") (name "Net-(D5-Pad+)") (class "Default")
      (node (ref "D5") (pin "+") (pinfunction "+_+") (pintype "passive"))
      (node (ref "R22") (pin "1") (pinfunction "1_1") (pintype "passive"))
    )
    (net (code "20") (name "Net-(D6-Pad+)") (class "Default")
      (node (ref "D6") (pin "+") (pinfunction "+_+") (pintype "passive"))
      (node (ref "R51") (pin "1") (pinfunction "1_1") (pintype "passive"))
    )
    (net (code "21") (name "Net-(F2-Pad1)") (class "Default")
      (node (ref "F2") (pin "1") (pinfunction "1_1") (pintype "bidirectional"))
      (node (ref "L1") (pin "2") (pinfunction "2_2") (pintype "passive"))
    )
    (net (code "22") (name "Net-(Q1-G)") (class "Default")
      (node (ref "Q1") (pin "4") (pinfunction "G_4") (pintype "passive"))
      (node (ref "Q2") (pin "3") (pinfunction "D_3") (pintype "passive"))
      (node (ref "R32") (pin "2") (pinfunction "2_2") (pintype "passive"))
    )
    (net (code "23") (name "Net-(Q2-G)") (class "Default")
      (node (ref "C42") (pin "1") (pinfunction "1_1") (pintype "passive"))
      (node (ref "Q2") (pin "1") (pinfunction "G_1") (pintype "passive"))
      (node (ref "R46") (pin "2") (pinfunction "2_2") (pintype "passive"))
      (node (ref "R48") (pin "2") (pinfunction "2_2") (pintype "passive"))
    )
    (net (code "24") (name "Net-(R3-Pad1)") (class "Default")
      (node (ref "R3") (pin "1") (pinfunction "1_1") (pintype "passive"))
      (node (ref "SW3") (pin "CH2A") (pinfunction "CH2A_CH2A") (pintype "bidirectional"))
    )
    (net (code "25") (name "Net-(R3-Pad2)") (class "Default")
      (node (ref "R3") (pin "2") (pinfunction "2_2") (pintype "passive"))
      (node (ref "SW3") (pin "CH1A") (pinfunction "CH1A_CH1A") (pintype "bidirectional"))
    )
    (net (code "26") (name "Net-(R39-Pad1)") (class "Default")
      (node (ref "R39") (pin "1") (pinfunction "1_1") (pintype "passive"))
      (node (ref "SW4") (pin "CH2A") (pinfunction "CH2A_CH2A") (pintype "bidirectional"))
    )
    (net (code "27") (name "Net-(R39-Pad2)") (class "Default")
      (node (ref "R39") (pin "2") (pinfunction "2_2") (pintype "passive"))
      (node (ref "SW4") (pin "CH1A") (pinfunction "CH1A_CH1A") (pintype "bidirectional"))
    )
    (net (code "28") (name "Net-(SW1-A)") (class "Default")
      (node (ref "R47") (pin "1") (pinfunction "1_1") (pintype "passive"))
      (node (ref "SW1") (pin "1") (pinfunction "A_1") (pintype "bidirectional"))
    )
    (net (code "29") (name "Net-(SW1-COM)") (class "Default")
      (node (ref "R48") (pin "1") (pinfunction "1_1") (pintype "passive"))
      (node (ref "R51") (pin "2") (pinfunction "2_2") (pintype "passive"))
      (node (ref "SW1") (pin "2") (pinfunction "COM_2") (pintype "bidirectional"))
    )
    (net (code "30") (name "Net-(U1-STBY)") (class "Default")
      (node (ref "R50") (pin "1") (pinfunction "1_1") (pintype "passive"))
      (node (ref "U1") (pin "8") (pinfunction "STBY_8") (pintype "bidirectional"))
    )
    (net (code "31") (name "Net-(U2-EN)") (class "Default")
      (node (ref "R1") (pin "1") (pinfunction "1_1") (pintype "passive"))
      (node (ref "U2") (pin "7") (pinfunction "VREF2_7") (pintype "bidirectional"))
      (node (ref "U2") (pin "8") (pinfunction "EN_8") (pintype "bidirectional"))
    )
    (net (code "32") (name "Net-(U3-STBY)") (class "Default")
      (node (ref "R49") (pin "1") (pinfunction "1_1") (pintype "passive"))
      (node (ref "U3") (pin "8") (pinfunction "STBY_8") (pintype "bidirectional"))
    )
    (net (code "33") (name "Net-(U4-NCS)") (class "Default")
      (node (ref "R28") (pin "1") (pinfunction "1_1") (pintype "passive"))
      (node (ref "U4") (pin "13") (pinfunction "NCS_13") (pintype "bidirectional"))
    )
    (net (code "34") (name "Net-(U4-OSC1)") (class "Default")
      (node (ref "R56") (pin "1") (pinfunction "1_1") (pintype "passive"))
      (node (ref "U4") (pin "6") (pinfunction "OSC1_6") (pintype "bidirectional"))
    )
    (net (code "35") (name "Net-(U4-SCK)") (class "Default")
      (node (ref "R27") (pin "1") (pinfunction "1_1") (pintype "passive"))
      (node (ref "U4") (pin "10") (pinfunction "SCK_10") (pintype "bidirectional"))
    )
    (net (code "36") (name "Net-(U4-SDI)") (class "Default")
      (node (ref "R26") (pin "1") (pinfunction "1_1") (pintype "passive"))
      (node (ref "U4") (pin "11") (pinfunction "SDI_11") (pintype "bidirectional"))
    )
    (net (code "37") (name "Net-(U4-SDO)") (class "Default")
      (node (ref "R25") (pin "1") (pinfunction "1_1") (pintype "passive"))
      (node (ref "U4") (pin "12") (pinfunction "SDO_12") (pintype "bidirectional"))
    )
    (net (code "38") (name "Net-(U4-~{INT})") (class "Default")
      (node (ref "R29") (pin "1") (pinfunction "1_1") (pintype "passive"))
      (node (ref "U4") (pin "4") (pinfunction "~{INT}_4") (pintype "bidirectional"))
    )
    (net (code "39") (name "Net-(U8-VOUT)") (class "Default")
      (node (ref "R30") (pin "1") (pinfunction "1_1") (pintype "passive"))
      (node (ref "U8") (pin "5") (pinfunction "VOUT_5") (pintype "bidirectional"))
    )
    (net (code "40") (name "Net-(U9-WP)") (class "Default")
      (node (ref "TP1") (pin "T") (pinfunction "T_T") (pintype "bidirectional"))
      (node (ref "U9") (pin "5") (pinfunction "WP_5") (pintype "bidirectional"))
    )
    (net (code "41") (name "Net-(U11-NCS)") (class "Default")
      (node (ref "R37") (pin "1") (pinfunction "1_1") (pintype "passive"))
      (node (ref "U11") (pin "13") (pinfunction "NCS_13") (pintype "bidirectional"))
    )
    (net (code "42") (name "Net-(U11-OSC1)") (class "Default")
      (node (ref "R55") (pin "1") (pinfunction "1_1") (pintype "passive"))
      (node (ref "U11") (pin "6") (pinfunction "OSC1_6") (pintype "bidirectional"))
    )
    (net (code "43") (name "Net-(U11-SCK)") (class "Default")
      (node (ref "R36") (pin "1") (pinfunction "1_1") (pintype "passive"))
      (node (ref "U11") (pin "10") (pinfunction "SCK_10") (pintype "bidirectional"))
    )
    (net (code "44") (name "Net-(U11-SDI)") (class "Default")
      (node (ref "R35") (pin "1") (pinfunction "1_1") (pintype "passive"))
      (node (ref "U11") (pin "11") (pinfunction "SDI_11") (pintype "bidirectional"))
    )
    (net (code "45") (name "Net-(U11-SDO)") (class "Default")
      (node (ref "R34") (pin "1") (pinfunction "1_1") (pintype "passive"))
      (node (ref "U11") (pin "12") (pinfunction "SDO_12") (pintype "bidirectional"))
    )
    (net (code "46") (name "Net-(U11-~{INT})") (class "Default")
      (node (ref "R38") (pin "1") (pinfunction "1_1") (pintype "passive"))
      (node (ref "U11") (pin "4") (pinfunction "~{INT}_4") (pintype "bidirectional"))
    )
    (net (code "47") (name "Net-(U14-BOOT)") (class "Default")
      (node (ref "C113") (pin "1") (pinfunction "1_1") (pintype "passive"))
      (node (ref "U14") (pin "6") (pinfunction "BOOT_6") (pintype "bidirectional"))
    )
    (net (code "48") (name "Net-(U14-EN)") (class "Default")
      (node (ref "R201") (pin "2") (pinfunction "2_2") (pintype "passive"))
      (node (ref "R7") (pin "1") (pinfunction "1_1") (pintype "passive"))
      (node (ref "U14") (pin "5") (pinfunction "EN_5") (pintype "bidirectional"))
    )
    (net (code "49") (name "Net-(U14-FB)") (class "Default")
      (node (ref "C114") (pin "1") (pinfunction "1_1") (pintype "passive"))
      (node (ref "R115") (pin "2") (pinfunction "2_2") (pintype "passive"))
      (node (ref "R66") (pin "2") (pinfunction "2_2") (pintype "passive"))
      (node (ref "U14") (pin "4") (pinfunction "FB_4") (pintype "bidirectional"))
    )
    (net (code "50") (name "Net-(U14-SW)") (class "Default")
      (node (ref "C113") (pin "2") (pinfunction "2_2") (pintype "passive"))
      (node (ref "L6") (pin "1") (pinfunction "1_1") (pintype "passive"))
      (node (ref "U14") (pin "2") (pinfunction "SW_2") (pintype "bidirectional"))
    )
    (net (code "51") (name "Net-(U14-VIN)") (class "Default")
      (node (ref "C108") (pin "2") (pinfunction "2_2") (pintype "passive"))
      (node (ref "C118") (pin "+") (pinfunction "+_+") (pintype "passive"))
      (node (ref "C72") (pin "2") (pinfunction "2_2") (pintype "passive"))
      (node (ref "F6") (pin "2") (pinfunction "2_2") (pintype "bidirectional"))
      (node (ref "R7") (pin "2") (pinfunction "2_2") (pintype "passive"))
      (node (ref "U14") (pin "3") (pinfunction "VIN_3") (pintype "bidirectional"))
    )
    (net (code "52") (name "Net-(U15-OSCI)") (class "Default")
      (node (ref "C5") (pin "2") (pinfunction "2_2") (pintype "passive"))
      (node (ref "U15") (pin "1") (pinfunction "OSCI_1") (pintype "bidirectional"))
      (node (ref "X2") (pin "2") (pinfunction "2_2") (pintype "passive"))
    )
    (net (code "53") (name "Net-(U15-OSCO)") (class "Default")
      (node (ref "C4") (pin "2") (pinfunction "2_2") (pintype "passive"))
      (node (ref "U15") (pin "2") (pinfunction "OSCO_2") (pintype "bidirectional"))
      (node (ref "X2") (pin "1") (pinfunction "1_1") (pintype "passive"))
    )
    (net (code "54") (name "Net-(U15-VDD)") (class "Default")
      (node (ref "C6") (pin "1") (pinfunction "1_1") (pintype "passive"))
      (node (ref "U15") (pin "8") (pinfunction "VDD_8") (pintype "bidirectional"))
      (node (ref "U5") (pin "3") (pinfunction "P$3_3") (pintype "bidirectional"))
    )
    (net (code "55") (name "Net-(X1-ENABLE)") (class "Default")
      (node (ref "R8") (pin "2") (pinfunction "2_2") (pintype "passive"))
      (node (ref "X1") (pin "1") (pinfunction "ENABLE_1") (pintype "bidirectional"))
    )
    (net (code "56") (name "Net-(X1-OUT)") (class "Default")
      (node (ref "R55") (pin "2") (pinfunction "2_2") (pintype "passive"))
      (node (ref "X1") (pin "3") (pinfunction "OUT_3") (pintype "bidirectional"))
    )
    (net (code "57") (name "Net-(X1-VDD)") (class "Default")
      (node (ref "C24") (pin "2") (pinfunction "2_2") (pintype "passive"))
      (node (ref "C3") (pin "2") (pinfunction "2_2") (pintype "passive"))
      (node (ref "L3") (pin "1") (pinfunction "1_1") (pintype "passive"))
      (node (ref "R54") (pin "1") (pinfunction "1_1") (pintype "passive"))
      (node (ref "R8") (pin "1") (pinfunction "1_1") (pintype "passive"))
      (node (ref "X1") (pin "4") (pinfunction "VDD_4") (pintype "bidirectional"))
      (node (ref "X3") (pin "4") (pinfunction "VDD_4") (pintype "bidirectional"))
    )
    (net (code "58") (name "Net-(X3-ENABLE)") (class "Default")
      (node (ref "R54") (pin "2") (pinfunction "2_2") (pintype "passive"))
      (node (ref "X3") (pin "1") (pinfunction "ENABLE_1") (pintype "bidirectional"))
    )
    (net (code "59") (name "Net-(X3-OUT)") (class "Default")
      (node (ref "R56") (pin "2") (pinfunction "2_2") (pintype "passive"))
      (node (ref "X3") (pin "3") (pinfunction "OUT_3") (pintype "bidirectional"))
    )
    (net (code "60") (name "SCL_H") (class "Default")
      (node (ref "J3") (pin "1") (pinfunction "1_1") (pintype "bidirectional"))
      (node (ref "J4") (pin "1") (pinfunction "1_1") (pintype "bidirectional"))
      (node (ref "R2") (pin "1") (pinfunction "1_1") (pintype "passive"))
      (node (ref "U2") (pin "6") (pinfunction "SCL2_6") (pintype "bidirectional"))
    )
    (net (code "61") (name "SCL_RPI") (class "Default")
      (node (ref "R5") (pin "1") (pinfunction "1_1") (pintype "passive"))
      (node (ref "U10") (pin "5") (pinfunction "GPIO3/SCL1_5") (pintype "bidirectional"))
      (node (ref "U15") (pin "6") (pinfunction "SCL_6") (pintype "bidirectional"))
      (node (ref "U2") (pin "3") (pinfunction "SCL1_3") (pintype "bidirectional"))
      (node (ref "U9") (pin "1") (pinfunction "SCL_1") (pintype "bidirectional"))
    )
    (net (code "62") (name "SDA_H") (class "Default")
      (node (ref "J3") (pin "2") (pinfunction "2_2") (pintype "bidirectional"))
      (node (ref "J4") (pin "2") (pinfunction "2_2") (pintype "bidirectional"))
      (node (ref "R4") (pin "1") (pinfunction "1_1") (pintype "passive"))
      (node (ref "U2") (pin "5") (pinfunction "SDA2_5") (pintype "bidirectional"))
    )
    (net (code "63") (name "SDA_RPI") (class "Default")
      (node (ref "R6") (pin "1") (pinfunction "1_1") (pintype "passive"))
      (node (ref "U10") (pin "3") (pinfunction "GPIO2/SDA1_3") (pintype "bidirectional"))
      (node (ref "U15") (pin "5") (pinfunction "SDA_5") (pintype "bidirectional"))
      (node (ref "U2") (pin "4") (pinfunction "SDA1_4") (pintype "bidirectional"))
      (node (ref "U9") (pin "3") (pinfunction "SDA_3") (pintype "bidirectional"))
    )
    (net (code "64") (name "SPI0_CE0") (class "Default")
      (node (ref "R28") (pin "2") (pinfunction "2_2") (pintype "passive"))
      (node (ref "U10") (pin "24") (pinfunction "~{CE0}/GPIO8_24") (pintype "bidirectional"))
    )
    (net (code "65") (name "SPI0_CE1") (class "Default")
      (node (ref "R37") (pin "2") (pinfunction "2_2") (pintype "passive"))
      (node (ref "U10") (pin "26") (pinfunction "~{CE}/GPIO7_26") (pintype "bidirectional"))
    )
    (net (code "66") (name "SPI0_CLK") (class "Default")
      (node (ref "R27") (pin "2") (pinfunction "2_2") (pintype "passive"))
      (node (ref "R36") (pin "2") (pinfunction "2_2") (pintype "passive"))
      (node (ref "U10") (pin "23") (pinfunction "GPIO11/SCLK_23") (pintype "bidirectional"))
    )
    (net (code "67") (name "SPI0_MISO") (class "Default")
      (node (ref "R25") (pin "2") (pinfunction "2_2") (pintype "passive"))
      (node (ref "R34") (pin "2") (pinfunction "2_2") (pintype "passive"))
      (node (ref "U10") (pin "21") (pinfunction "GPIO9/MISO_21") (pintype "bidirectional"))
    )
    (net (code "68") (name "SPI0_MOSI") (class "Default")
      (node (ref "R26") (pin "2") (pinfunction "2_2") (pintype "passive"))
      (node (ref "R35") (pin "2") (pinfunction "2_2") (pintype "passive"))
      (node (ref "U10") (pin "19") (pinfunction "GPIO10/MOSI_19") (pintype "bidirectional"))
    )
    (net (code "69") (name "VCC5V2") (class "Default")
      (node (ref "C133") (pin "2") (pinfunction "2_2") (pintype "passive"))
      (node (ref "C134") (pin "2") (pinfunction "2_2") (pintype "passive"))
      (node (ref "C69") (pin "2") (pinfunction "2_2") (pintype "passive"))
      (node (ref "C73") (pin "2") (pinfunction "2_2") (pintype "passive"))
      (node (ref "C9") (pin "2") (pinfunction "2_2") (pintype "passive"))
      (node (ref "D66") (pin "2") (pinfunction "-_2") (pintype "bidirectional"))
      (node (ref "L4") (pin "1") (pinfunction "1_1") (pintype "passive"))
      (node (ref "L5") (pin "1") (pinfunction "1_1") (pintype "passive"))
      (node (ref "L6") (pin "2") (pinfunction "2_2") (pintype "passive"))
      (node (ref "R21") (pin "2") (pinfunction "2_2") (pintype "passive"))
      (node (ref "R64") (pin "2") (pinfunction "2_2") (pintype "passive"))
      (node (ref "VCC5VSENSOR") (pin "T") (pinfunction "T_T") (pintype "bidirectional"))
    )
    (net (code "70") (name "VCC_3V3") (class "Default")
      (node (ref "C2") (pin "2") (pinfunction "2_2") (pintype "passive"))
      (node (ref "C23") (pin "2") (pinfunction "2_2") (pintype "passive"))
      (node (ref "C26") (pin "2") (pinfunction "2_2") (pintype "passive"))
      (node (ref "C27") (pin "2") (pinfunction "2_2") (pintype "passive"))
      (node (ref "C29") (pin "2") (pinfunction "2_2") (pintype "passive"))
      (node (ref "C30") (pin "1") (pinfunction "1_1") (pintype "passive"))
      (node (ref "C37") (pin "2") (pinfunction "2_2") (pintype "passive"))
      (node (ref "C38") (pin "2") (pinfunction "2_2") (pintype "passive"))
      (node (ref "L3") (pin "2") (pinfunction "2_2") (pintype "passive"))
      (node (ref "R22") (pin "2") (pinfunction "2_2") (pintype "passive"))
      (node (ref "R30") (pin "2") (pinfunction "2_2") (pintype "passive"))
      (node (ref "R5") (pin "2") (pinfunction "2_2") (pintype "passive"))
      (node (ref "R6") (pin "2") (pinfunction "2_2") (pintype "passive"))
      (node (ref "U1") (pin "5") (pinfunction "VIO_5") (pintype "bidirectional"))
      (node (ref "U11") (pin "14") (pinfunction "VDD_14") (pintype "bidirectional"))
      (node (ref "U2") (pin "2") (pinfunction "VREF1_2") (pintype "bidirectional"))
      (node (ref "U3") (pin "5") (pinfunction "VIO_5") (pintype "bidirectional"))
      (node (ref "U4") (pin "14") (pinfunction "VDD_14") (pintype "bidirectional"))
      (node (ref "U5") (pin "1") (pinfunction "P$1_1") (pintype "bidirectional"))
      (node (ref "U9") (pin "4") (pinfunction "VCC_4") (pintype "bidirectional"))
    )
    (net (code "71") (name "VCC_5V") (class "Default")
      (node (ref "C1") (pin "2") (pinfunction "2_2") (pintype "passive"))
      (node (ref "C28") (pin "2") (pinfunction "2_2") (pintype "passive"))
      (node (ref "C31") (pin "2") (pinfunction "2_2") (pintype "passive"))
      (node (ref "C36") (pin "2") (pinfunction "2_2") (pintype "passive"))
      (node (ref "C43") (pin "1") (pinfunction "1_1") (pintype "passive"))
      (node (ref "D9") (pin "-") (pinfunction "-_-") (pintype "passive"))
      (node (ref "F2") (pin "2") (pinfunction "2_2") (pintype "bidirectional"))
      (node (ref "L4") (pin "2") (pinfunction "2_2") (pintype "passive"))
      (node (ref "L5") (pin "2") (pinfunction "2_2") (pintype "passive"))
      (node (ref "Q1") (pin "1") (pinfunction "S_1") (pintype "passive"))
      (node (ref "Q1") (pin "2") (pinfunction "S_2") (pintype "passive"))
      (node (ref "Q1") (pin "3") (pinfunction "S_3") (pintype "passive"))
      (node (ref "R1") (pin "2") (pinfunction "2_2") (pintype "passive"))
      (node (ref "R2") (pin "2") (pinfunction "2_2") (pintype "passive"))
      (node (ref "R32") (pin "1") (pinfunction "1_1") (pintype "passive"))
      (node (ref "R4") (pin "2") (pinfunction "2_2") (pintype "passive"))
      (node (ref "R47") (pin "2") (pinfunction "2_2") (pintype "passive"))
      (node (ref "U1") (pin "3") (pinfunction "VCC_3") (pintype "bidirectional"))
      (node (ref "U3") (pin "3") (pinfunction "VCC_3") (pintype "bidirectional"))
      (node (ref "U8") (pin "1") (pinfunction "VIN_1") (pintype "bidirectional"))
      (node (ref "U8") (pin "3") (pinfunction "CE_3") (pintype "bidirectional"))
    )
    (net (code "72") (name "VCC_EXT") (class "Default")
      (node (ref "D1") (pin "1") (pinfunction "+_1") (pintype "passive"))
      (node (ref "J6") (pin "1") (pinfunction "1_1") (pintype "bidirectional"))
    )
    (net (code "73") (name "VCC_G") (class "Default")
      (node (ref "C19") (pin "2") (pinfunction "2_2") (pintype "passive"))
      (node (ref "C20") (pin "2") (pinfunction "2_2") (pintype "passive"))
      (node (ref "C21") (pin "2") (pinfunction "2_2") (pintype "passive"))
      (node (ref "C22") (pin "2") (pinfunction "2_2") (pintype "passive"))
      (node (ref "J3") (pin "3") (pinfunction "3_3") (pintype "bidirectional"))
      (node (ref "J4") (pin "3") (pinfunction "3_3") (pintype "bidirectional"))
      (node (ref "L1") (pin "1") (pinfunction "1_1") (pintype "passive"))
    )
    (net (code "74") (name "unconnected-(SW3-PadCH1B)") (class "Default")
      (node (ref "SW3") (pin "CH1B") (pinfunction "CH1B_CH1B") (pintype "bidirectional"))
    )
    (net (code "75") (name "unconnected-(SW3-PadCH2B)") (class "Default")
      (node (ref "SW3") (pin "CH2B") (pinfunction "CH2B_CH2B") (pintype "bidirectional"))
    )
    (net (code "76") (name "unconnected-(SW4-PadCH1B)") (class "Default")
      (node (ref "SW4") (pin "CH1B") (pinfunction "CH1B_CH1B") (pintype "bidirectional"))
    )
    (net (code "77") (name "unconnected-(SW4-PadCH2B)") (class "Default")
      (node (ref "SW4") (pin "CH2B") (pinfunction "CH2B_CH2B") (pintype "bidirectional"))
    )
    (net (code "78") (name "unconnected-(U4-CLKO{slash}SOF-Pad3)") (class "Default")
      (node (ref "U4") (pin "3") (pinfunction "CLKO/SOF_3") (pintype "bidirectional"))
    )
    (net (code "79") (name "unconnected-(U4-OSC2-Pad5)") (class "Default")
      (node (ref "U4") (pin "5") (pinfunction "OSC2_5") (pintype "bidirectional"))
    )
    (net (code "80") (name "unconnected-(U4-~{INT0}-Pad9)") (class "Default")
      (node (ref "U4") (pin "9") (pinfunction "~{INT0}_9") (pintype "bidirectional"))
    )
    (net (code "81") (name "unconnected-(U4-~{INT1}-Pad8)") (class "Default")
      (node (ref "U4") (pin "8") (pinfunction "~{INT1}_8") (pintype "bidirectional"))
    )
    (net (code "82") (name "unconnected-(U6-P$3-Pad3)") (class "Default")
      (node (ref "U6") (pin "3") (pinfunction "P$3_3") (pintype "bidirectional"))
    )
    (net (code "83") (name "unconnected-(U7-P$3-Pad3)") (class "Default")
      (node (ref "U7") (pin "3") (pinfunction "P$3_3") (pintype "bidirectional"))
    )
    (net (code "84") (name "unconnected-(U8-NC-Pad4)") (class "Default")
      (node (ref "U8") (pin "4") (pinfunction "NC_4") (pintype "bidirectional"))
    )
    (net (code "85") (name "unconnected-(U10-GEN4{slash}GPIO23-Pad16)") (class "Default")
      (node (ref "U10") (pin "16") (pinfunction "GEN4/GPIO23_16") (pintype "bidirectional"))
    )
    (net (code "86") (name "unconnected-(U10-GPIO4{slash}GCKL-Pad7)") (class "Default")
      (node (ref "U10") (pin "7") (pinfunction "GPIO4/GCKL_7") (pintype "bidirectional"))
    )
    (net (code "87") (name "unconnected-(U10-GPIO5-Pad29)") (class "Default")
      (node (ref "U10") (pin "29") (pinfunction "GPIO5_29") (pintype "bidirectional"))
    )
    (net (code "88") (name "unconnected-(U10-GPIO6-Pad31)") (class "Default")
      (node (ref "U10") (pin "31") (pinfunction "GPIO6_31") (pintype "bidirectional"))
    )
    (net (code "89") (name "unconnected-(U10-GPIO12-Pad32)") (class "Default")
      (node (ref "U10") (pin "32") (pinfunction "GPIO12_32") (pintype "bidirectional"))
    )
    (net (code "90") (name "unconnected-(U10-GPIO13-Pad33)") (class "Default")
      (node (ref "U10") (pin "33") (pinfunction "GPIO13_33") (pintype "bidirectional"))
    )
    (net (code "91") (name "unconnected-(U10-GPIO16-Pad36)") (class "Default")
      (node (ref "U10") (pin "36") (pinfunction "GPIO16_36") (pintype "bidirectional"))
    )
    (net (code "92") (name "unconnected-(U10-GPIO17{slash}GEN0-Pad11)") (class "Default")
      (node (ref "U10") (pin "11") (pinfunction "GPIO17/GEN0_11") (pintype "bidirectional"))
    )
    (net (code "93") (name "unconnected-(U10-GPIO18-Pad12)") (class "Default")
      (node (ref "U10") (pin "12") (pinfunction "GPIO18_12") (pintype "bidirectional"))
    )
    (net (code "94") (name "unconnected-(U10-GPIO19-Pad35)") (class "Default")
      (node (ref "U10") (pin "35") (pinfunction "GPIO19_35") (pintype "bidirectional"))
    )
    (net (code "95") (name "unconnected-(U10-GPIO20-Pad38)") (class "Default")
      (node (ref "U10") (pin "38") (pinfunction "GPIO20_38") (pintype "bidirectional"))
    )
    (net (code "96") (name "unconnected-(U10-GPIO21-Pad40)") (class "Default")
      (node (ref "U10") (pin "40") (pinfunction "GPIO21_40") (pintype "bidirectional"))
    )
    (net (code "97") (name "unconnected-(U10-GPIO22{slash}GEN3-Pad15)") (class "Default")
      (node (ref "U10") (pin "15") (pinfunction "GPIO22/GEN3_15") (pintype "bidirectional"))
    )
    (net (code "98") (name "unconnected-(U10-GPIO26-Pad37)") (class "Default")
      (node (ref "U10") (pin "37") (pinfunction "GPIO26_37") (pintype "bidirectional"))
    )
    (net (code "99") (name "unconnected-(U10-GPIO27{slash}GEN2-Pad13)") (class "Default")
      (node (ref "U10") (pin "13") (pinfunction "GPIO27/GEN2_13") (pintype "bidirectional"))
    )
    (net (code "100") (name "unconnected-(U10-ID_SC-Pad28)") (class "Default")
      (node (ref "U10") (pin "28") (pinfunction "ID_SC_28") (pintype "bidirectional"))
    )
    (net (code "101") (name "unconnected-(U10-ID_SD-Pad27)") (class "Default")
      (node (ref "U10") (pin "27") (pinfunction "ID_SD_27") (pintype "bidirectional"))
    )
    (net (code "102") (name "unconnected-(U10-RXD0{slash}GPIO15-Pad10)") (class "Default")
      (node (ref "U10") (pin "10") (pinfunction "RXD0/GPIO15_10") (pintype "bidirectional"))
    )
    (net (code "103") (name "unconnected-(U10-TXD0{slash}GPIO14-Pad8)") (class "Default")
      (node (ref "U10") (pin "8") (pinfunction "TXD0/GPIO14_8") (pintype "bidirectional"))
    )
    (net (code "104") (name "unconnected-(U11-CLKO{slash}SOF-Pad3)") (class "Default")
      (node (ref "U11") (pin "3") (pinfunction "CLKO/SOF_3") (pintype "bidirectional"))
    )
    (net (code "105") (name "unconnected-(U11-OSC2-Pad5)") (class "Default")
      (node (ref "U11") (pin "5") (pinfunction "OSC2_5") (pintype "bidirectional"))
    )
    (net (code "106") (name "unconnected-(U11-~{INT0}-Pad9)") (class "Default")
      (node (ref "U11") (pin "9") (pinfunction "~{INT0}_9") (pintype "bidirectional"))
    )
    (net (code "107") (name "unconnected-(U11-~{INT1}-Pad8)") (class "Default")
      (node (ref "U11") (pin "8") (pinfunction "~{INT1}_8") (pintype "bidirectional"))
    )
    (net (code "108") (name "unconnected-(U12-P$3-Pad3)") (class "Default")
      (node (ref "U12") (pin "3") (pinfunction "P$3_3") (pintype "bidirectional"))
    )
    (net (code "109") (name "unconnected-(U13-P$3-Pad3)") (class "Default")
      (node (ref "U13") (pin "3") (pinfunction "P$3_3") (pintype "bidirectional"))
    )
    (net (code "110") (name "unconnected-(U15-CLKOUT-Pad7)") (class "Default")
      (node (ref "U15") (pin "7") (pinfunction "CLKOUT_7") (pintype "bidirectional"))
    )
    (net (code "111") (name "unconnected-(U15-~{INT}-Pad3)") (class "Default")
      (node (ref "U15") (pin "3") (pinfunction "~{INT}_3") (pintype "bidirectional"))
    )
  )
)
